# PCB-SSB-2x2b.net
KiCad netlist of a schematic drawn in EAGLE
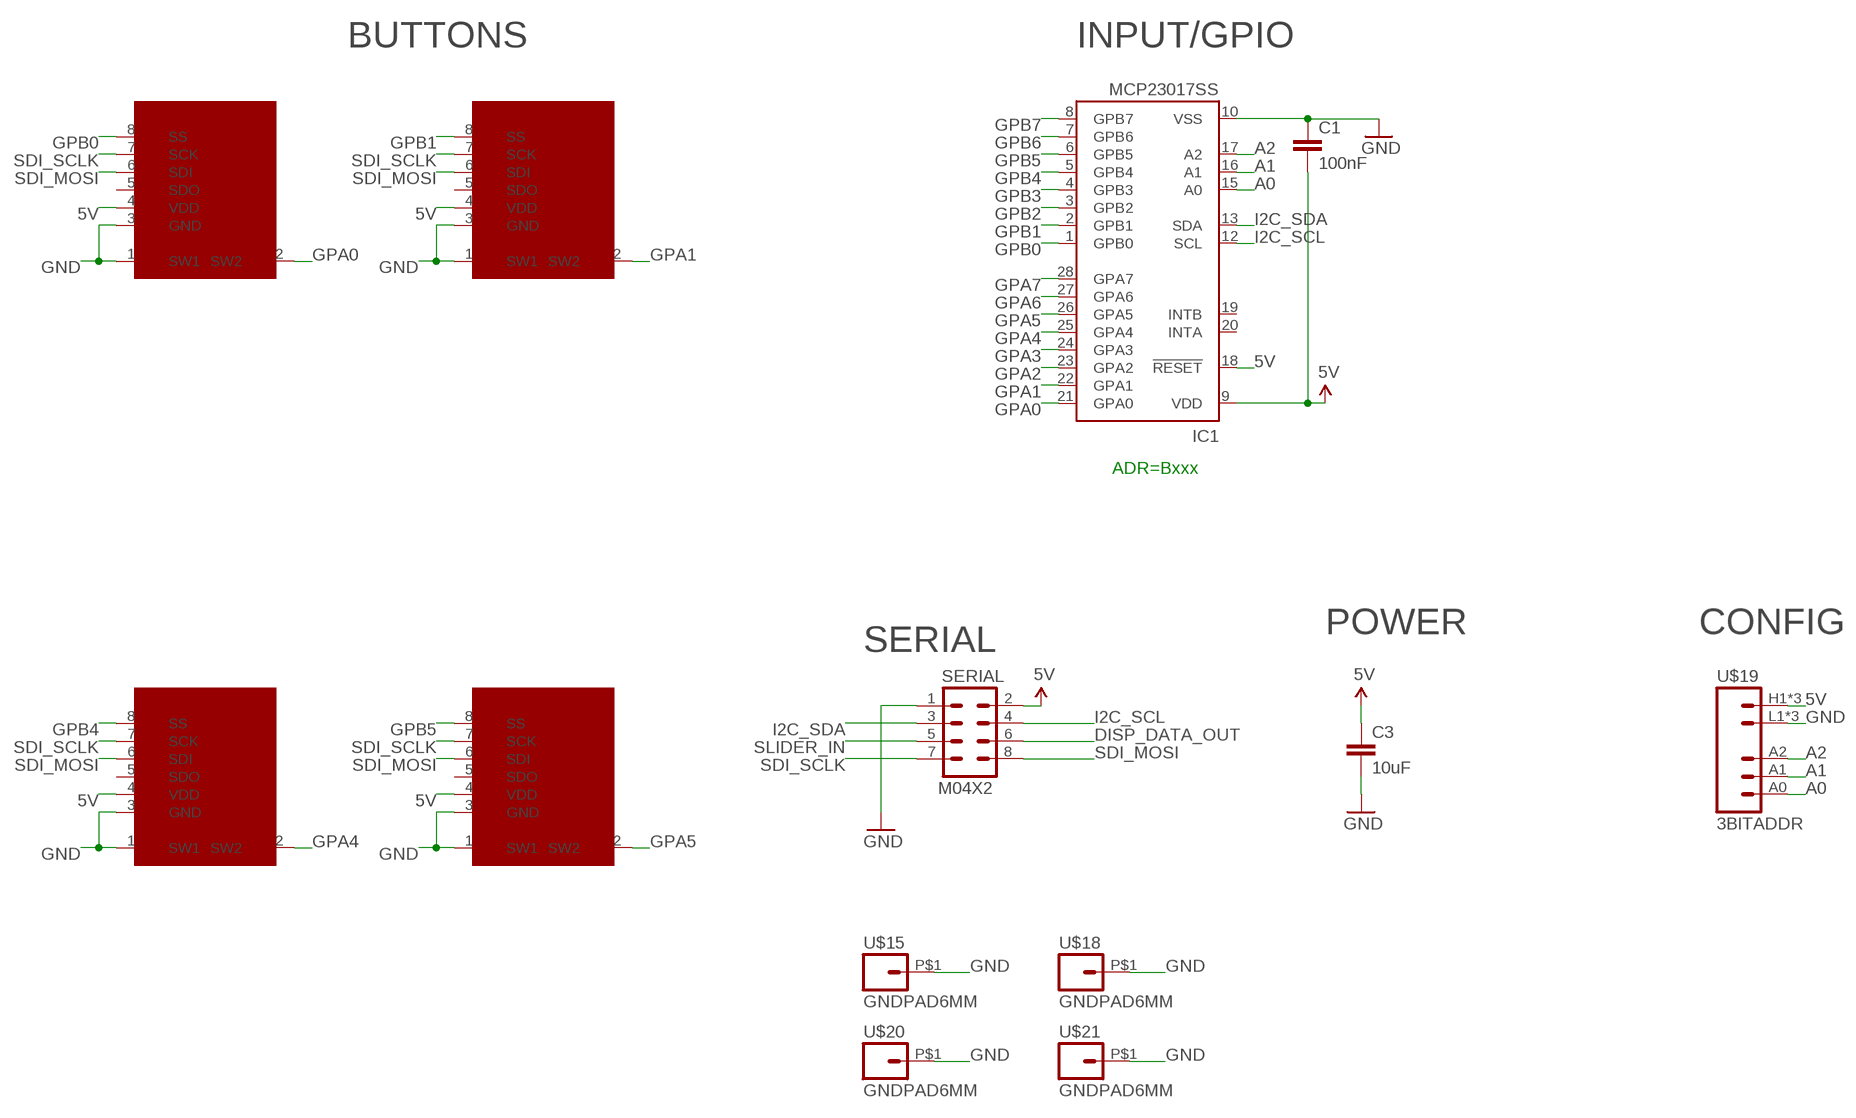
[diagram p0: schematic, sheet 1]

(export (version "E")
  (design (tool "Eeschema 10.0.6"))
  (components
    (comp (ref "C1")
      (value "100nF")
      (footprint "eagle-import:0603-CAP")
      (libsource (lib "eagle-import") (part "CAP0603-CAP"))
    )
    (comp (ref "C3")
      (value "10uF")
      (footprint "eagle-import:0805")
      (libsource (lib "eagle-import") (part "CAP0805"))
    )
    (comp (ref "IC1")
      (value "MCP23017SS")
      (footprint "eagle-import:SSOP28")
      (fields
        (field (name "MF") "MICROCHIP")
        (field (name "MPN") "MCP23017-E/SS")
        (field (name "MPN_1") "MCP23017-E/SS")
        (field (name "OC_FARNELL") "1467674")
        (field (name "OC_NEWARK") "31K2960")
      )
      (libsource (lib "eagle-import") (part "MCP23017SS"))
    )
    (comp (ref "SERIAL")
      (value "M04X2")
      (footprint "eagle-import:2X4")
      (libsource (lib "eagle-import") (part "M04X2"))
    )
    (comp (ref "SSW1")
      (value "SMART_SWITCHSMART_SWITCH_8PIN")
      (footprint "eagle-import:SMART_SWITCH")
      (libsource (lib "eagle-import") (part "SMART_SWITCHSMART_SWITCH_8PIN"))
    )
    (comp (ref "SSW2")
      (value "SMART_SWITCHSMART_SWITCH_8PIN")
      (footprint "eagle-import:SMART_SWITCH")
      (libsource (lib "eagle-import") (part "SMART_SWITCHSMART_SWITCH_8PIN"))
    )
    (comp (ref "SSW5")
      (value "SMART_SWITCHSMART_SWITCH_8PIN")
      (footprint "eagle-import:SMART_SWITCH")
      (libsource (lib "eagle-import") (part "SMART_SWITCHSMART_SWITCH_8PIN"))
    )
    (comp (ref "SSW6")
      (value "SMART_SWITCHSMART_SWITCH_8PIN")
      (footprint "eagle-import:SMART_SWITCH")
      (libsource (lib "eagle-import") (part "SMART_SWITCHSMART_SWITCH_8PIN"))
    )
    (comp (ref "U$15")
      (value "GNDPAD6MM")
      (footprint "eagle-import:3.2MMPAD6MM")
      (libsource (lib "eagle-import") (part "GNDPAD6MM"))
    )
    (comp (ref "U$18")
      (value "GNDPAD6MM")
      (footprint "eagle-import:3.2MMPAD6MM")
      (libsource (lib "eagle-import") (part "GNDPAD6MM"))
    )
    (comp (ref "U$19")
      (value "3BITADDR")
      (footprint "eagle-import:3BITADDR")
      (libsource (lib "eagle-import") (part "3BITADDR"))
    )
    (comp (ref "U$20")
      (value "GNDPAD6MM")
      (footprint "eagle-import:3.2MMPAD6MM")
      (libsource (lib "eagle-import") (part "GNDPAD6MM"))
    )
    (comp (ref "U$21")
      (value "GNDPAD6MM")
      (footprint "eagle-import:3.2MMPAD6MM")
      (libsource (lib "eagle-import") (part "GNDPAD6MM"))
    )
  )
  (nets
    (net (code "1") (name "/A0") (class "Default")
      (node (ref "IC1") (pin "15") (pinfunction "A0_15") (pintype "input"))
      (node (ref "U$19") (pin "A0") (pinfunction "A0_A0") (pintype "passive"))
    )
    (net (code "2") (name "/A1") (class "Default")
      (node (ref "IC1") (pin "16") (pinfunction "A1_16") (pintype "input"))
      (node (ref "U$19") (pin "A1") (pinfunction "A1_A1") (pintype "passive"))
    )
    (net (code "3") (name "/A2") (class "Default")
      (node (ref "IC1") (pin "17") (pinfunction "A2_17") (pintype "input"))
      (node (ref "U$19") (pin "A2") (pinfunction "A2_A2") (pintype "passive"))
    )
    (net (code "4") (name "/DISP_DATA_OUT") (class "Default")
      (node (ref "SERIAL") (pin "6") (pinfunction "6_6") (pintype "passive"))
    )
    (net (code "5") (name "/GPA0") (class "Default")
      (node (ref "IC1") (pin "21") (pinfunction "GPA0_21") (pintype "bidirectional"))
      (node (ref "SSW1") (pin "2") (pinfunction "SW2_2") (pintype "bidirectional"))
    )
    (net (code "6") (name "/GPA1") (class "Default")
      (node (ref "IC1") (pin "22") (pinfunction "GPA1_22") (pintype "bidirectional"))
      (node (ref "SSW2") (pin "2") (pinfunction "SW2_2") (pintype "bidirectional"))
    )
    (net (code "7") (name "/GPA2") (class "Default")
      (node (ref "IC1") (pin "23") (pinfunction "GPA2_23") (pintype "bidirectional"))
    )
    (net (code "8") (name "/GPA3") (class "Default")
      (node (ref "IC1") (pin "24") (pinfunction "GPA3_24") (pintype "bidirectional"))
    )
    (net (code "9") (name "/GPA4") (class "Default")
      (node (ref "IC1") (pin "25") (pinfunction "GPA4_25") (pintype "bidirectional"))
      (node (ref "SSW5") (pin "2") (pinfunction "SW2_2") (pintype "bidirectional"))
    )
    (net (code "10") (name "/GPA5") (class "Default")
      (node (ref "IC1") (pin "26") (pinfunction "GPA5_26") (pintype "bidirectional"))
      (node (ref "SSW6") (pin "2") (pinfunction "SW2_2") (pintype "bidirectional"))
    )
    (net (code "11") (name "/GPA6") (class "Default")
      (node (ref "IC1") (pin "27") (pinfunction "GPA6_27") (pintype "bidirectional"))
    )
    (net (code "12") (name "/GPA7") (class "Default")
      (node (ref "IC1") (pin "28") (pinfunction "GPA7_28") (pintype "bidirectional"))
    )
    (net (code "13") (name "/GPB0") (class "Default")
      (node (ref "IC1") (pin "1") (pinfunction "GPB0_1") (pintype "bidirectional"))
      (node (ref "SSW1") (pin "8") (pinfunction "SS_8") (pintype "bidirectional"))
    )
    (net (code "14") (name "/GPB1") (class "Default")
      (node (ref "IC1") (pin "2") (pinfunction "GPB1_2") (pintype "bidirectional"))
      (node (ref "SSW2") (pin "8") (pinfunction "SS_8") (pintype "bidirectional"))
    )
    (net (code "15") (name "/GPB2") (class "Default")
      (node (ref "IC1") (pin "3") (pinfunction "GPB2_3") (pintype "bidirectional"))
    )
    (net (code "16") (name "/GPB3") (class "Default")
      (node (ref "IC1") (pin "4") (pinfunction "GPB3_4") (pintype "bidirectional"))
    )
    (net (code "17") (name "/GPB4") (class "Default")
      (node (ref "IC1") (pin "5") (pinfunction "GPB4_5") (pintype "bidirectional"))
      (node (ref "SSW5") (pin "8") (pinfunction "SS_8") (pintype "bidirectional"))
    )
    (net (code "18") (name "/GPB5") (class "Default")
      (node (ref "IC1") (pin "6") (pinfunction "GPB5_6") (pintype "bidirectional"))
      (node (ref "SSW6") (pin "8") (pinfunction "SS_8") (pintype "bidirectional"))
    )
    (net (code "19") (name "/GPB6") (class "Default")
      (node (ref "IC1") (pin "7") (pinfunction "GPB6_7") (pintype "bidirectional"))
    )
    (net (code "20") (name "/GPB7") (class "Default")
      (node (ref "IC1") (pin "8") (pinfunction "GPB7_8") (pintype "bidirectional"))
    )
    (net (code "21") (name "/I2C_SCL") (class "Default")
      (node (ref "IC1") (pin "12") (pinfunction "SCL_12") (pintype "input"))
      (node (ref "SERIAL") (pin "4") (pinfunction "4_4") (pintype "passive"))
    )
    (net (code "22") (name "/I2C_SDA") (class "Default")
      (node (ref "IC1") (pin "13") (pinfunction "SDA_13") (pintype "bidirectional"))
      (node (ref "SERIAL") (pin "3") (pinfunction "3_3") (pintype "passive"))
    )
    (net (code "23") (name "/SDI_MOSI") (class "Default")
      (node (ref "SERIAL") (pin "8") (pinfunction "8_8") (pintype "passive"))
      (node (ref "SSW1") (pin "6") (pinfunction "SDI_6") (pintype "bidirectional"))
      (node (ref "SSW2") (pin "6") (pinfunction "SDI_6") (pintype "bidirectional"))
      (node (ref "SSW5") (pin "6") (pinfunction "SDI_6") (pintype "bidirectional"))
      (node (ref "SSW6") (pin "6") (pinfunction "SDI_6") (pintype "bidirectional"))
    )
    (net (code "24") (name "/SDI_SCLK") (class "Default")
      (node (ref "SERIAL") (pin "7") (pinfunction "7_7") (pintype "passive"))
      (node (ref "SSW1") (pin "7") (pinfunction "SCK_7") (pintype "bidirectional"))
      (node (ref "SSW2") (pin "7") (pinfunction "SCK_7") (pintype "bidirectional"))
      (node (ref "SSW5") (pin "7") (pinfunction "SCK_7") (pintype "bidirectional"))
      (node (ref "SSW6") (pin "7") (pinfunction "SCK_7") (pintype "bidirectional"))
    )
    (net (code "25") (name "/SLIDER_IN") (class "Default")
      (node (ref "SERIAL") (pin "5") (pinfunction "5_5") (pintype "passive"))
    )
    (net (code "26") (name "5V") (class "Default")
      (node (ref "C1") (pin "2") (pinfunction "2_2") (pintype "passive"))
      (node (ref "C3") (pin "1") (pinfunction "1_1") (pintype "passive"))
      (node (ref "IC1") (pin "18") (pinfunction "~{RESET}_18") (pintype "input"))
      (node (ref "IC1") (pin "9") (pinfunction "VDD_9") (pintype "power_in"))
      (node (ref "SERIAL") (pin "2") (pinfunction "2_2") (pintype "passive"))
      (node (ref "SSW1") (pin "4") (pinfunction "VDD_4") (pintype "bidirectional"))
      (node (ref "SSW2") (pin "4") (pinfunction "VDD_4") (pintype "bidirectional"))
      (node (ref "SSW5") (pin "4") (pinfunction "VDD_4") (pintype "bidirectional"))
      (node (ref "SSW6") (pin "4") (pinfunction "VDD_4") (pintype "bidirectional"))
      (node (ref "U$19") (pin "H1") (pinfunction "VCC_H1") (pintype "passive"))
      (node (ref "U$19") (pin "H2") (pinfunction "VCC_H2") (pintype "passive"))
      (node (ref "U$19") (pin "H3") (pinfunction "VCC_H3") (pintype "passive"))
    )
    (net (code "27") (name "GND") (class "Default")
      (node (ref "C1") (pin "1") (pinfunction "1_1") (pintype "passive"))
      (node (ref "C3") (pin "2") (pinfunction "2_2") (pintype "passive"))
      (node (ref "IC1") (pin "10") (pinfunction "VSS_10") (pintype "power_in"))
      (node (ref "SERIAL") (pin "1") (pinfunction "1_1") (pintype "passive"))
      (node (ref "SSW1") (pin "1") (pinfunction "SW1_1") (pintype "bidirectional"))
      (node (ref "SSW1") (pin "3") (pinfunction "GND_3") (pintype "bidirectional"))
      (node (ref "SSW2") (pin "1") (pinfunction "SW1_1") (pintype "bidirectional"))
      (node (ref "SSW2") (pin "3") (pinfunction "GND_3") (pintype "bidirectional"))
      (node (ref "SSW5") (pin "1") (pinfunction "SW1_1") (pintype "bidirectional"))
      (node (ref "SSW5") (pin "3") (pinfunction "GND_3") (pintype "bidirectional"))
      (node (ref "SSW6") (pin "1") (pinfunction "SW1_1") (pintype "bidirectional"))
      (node (ref "SSW6") (pin "3") (pinfunction "GND_3") (pintype "bidirectional"))
      (node (ref "U$15") (pin "P$1") (pinfunction "1_P$1") (pintype "passive"))
      (node (ref "U$18") (pin "P$1") (pinfunction "1_P$1") (pintype "passive"))
      (node (ref "U$19") (pin "L1") (pinfunction "GND_L1") (pintype "passive"))
      (node (ref "U$19") (pin "L2") (pinfunction "GND_L2") (pintype "passive"))
      (node (ref "U$19") (pin "L3") (pinfunction "GND_L3") (pintype "passive"))
      (node (ref "U$20") (pin "P$1") (pinfunction "1_P$1") (pintype "passive"))
      (node (ref "U$21") (pin "P$1") (pinfunction "1_P$1") (pintype "passive"))
    )
    (net (code "28") (name "unconnected-(IC1-INTA-Pad20)") (class "Default")
      (node (ref "IC1") (pin "20") (pinfunction "INTA_20") (pintype "output"))
    )
    (net (code "29") (name "unconnected-(IC1-INTB-Pad19)") (class "Default")
      (node (ref "IC1") (pin "19") (pinfunction "INTB_19") (pintype "output"))
    )
    (net (code "30") (name "unconnected-(SSW1-SDO-Pad5)") (class "Default")
      (node (ref "SSW1") (pin "5") (pinfunction "SDO_5") (pintype "bidirectional"))
    )
    (net (code "31") (name "unconnected-(SSW2-SDO-Pad5)") (class "Default")
      (node (ref "SSW2") (pin "5") (pinfunction "SDO_5") (pintype "bidirectional"))
    )
    (net (code "32") (name "unconnected-(SSW5-SDO-Pad5)") (class "Default")
      (node (ref "SSW5") (pin "5") (pinfunction "SDO_5") (pintype "bidirectional"))
    )
    (net (code "33") (name "unconnected-(SSW6-SDO-Pad5)") (class "Default")
      (node (ref "SSW6") (pin "5") (pinfunction "SDO_5") (pintype "bidirectional"))
    )
  )
)
